# USB.net
KiCad netlist of a schematic drawn in Altium Designer
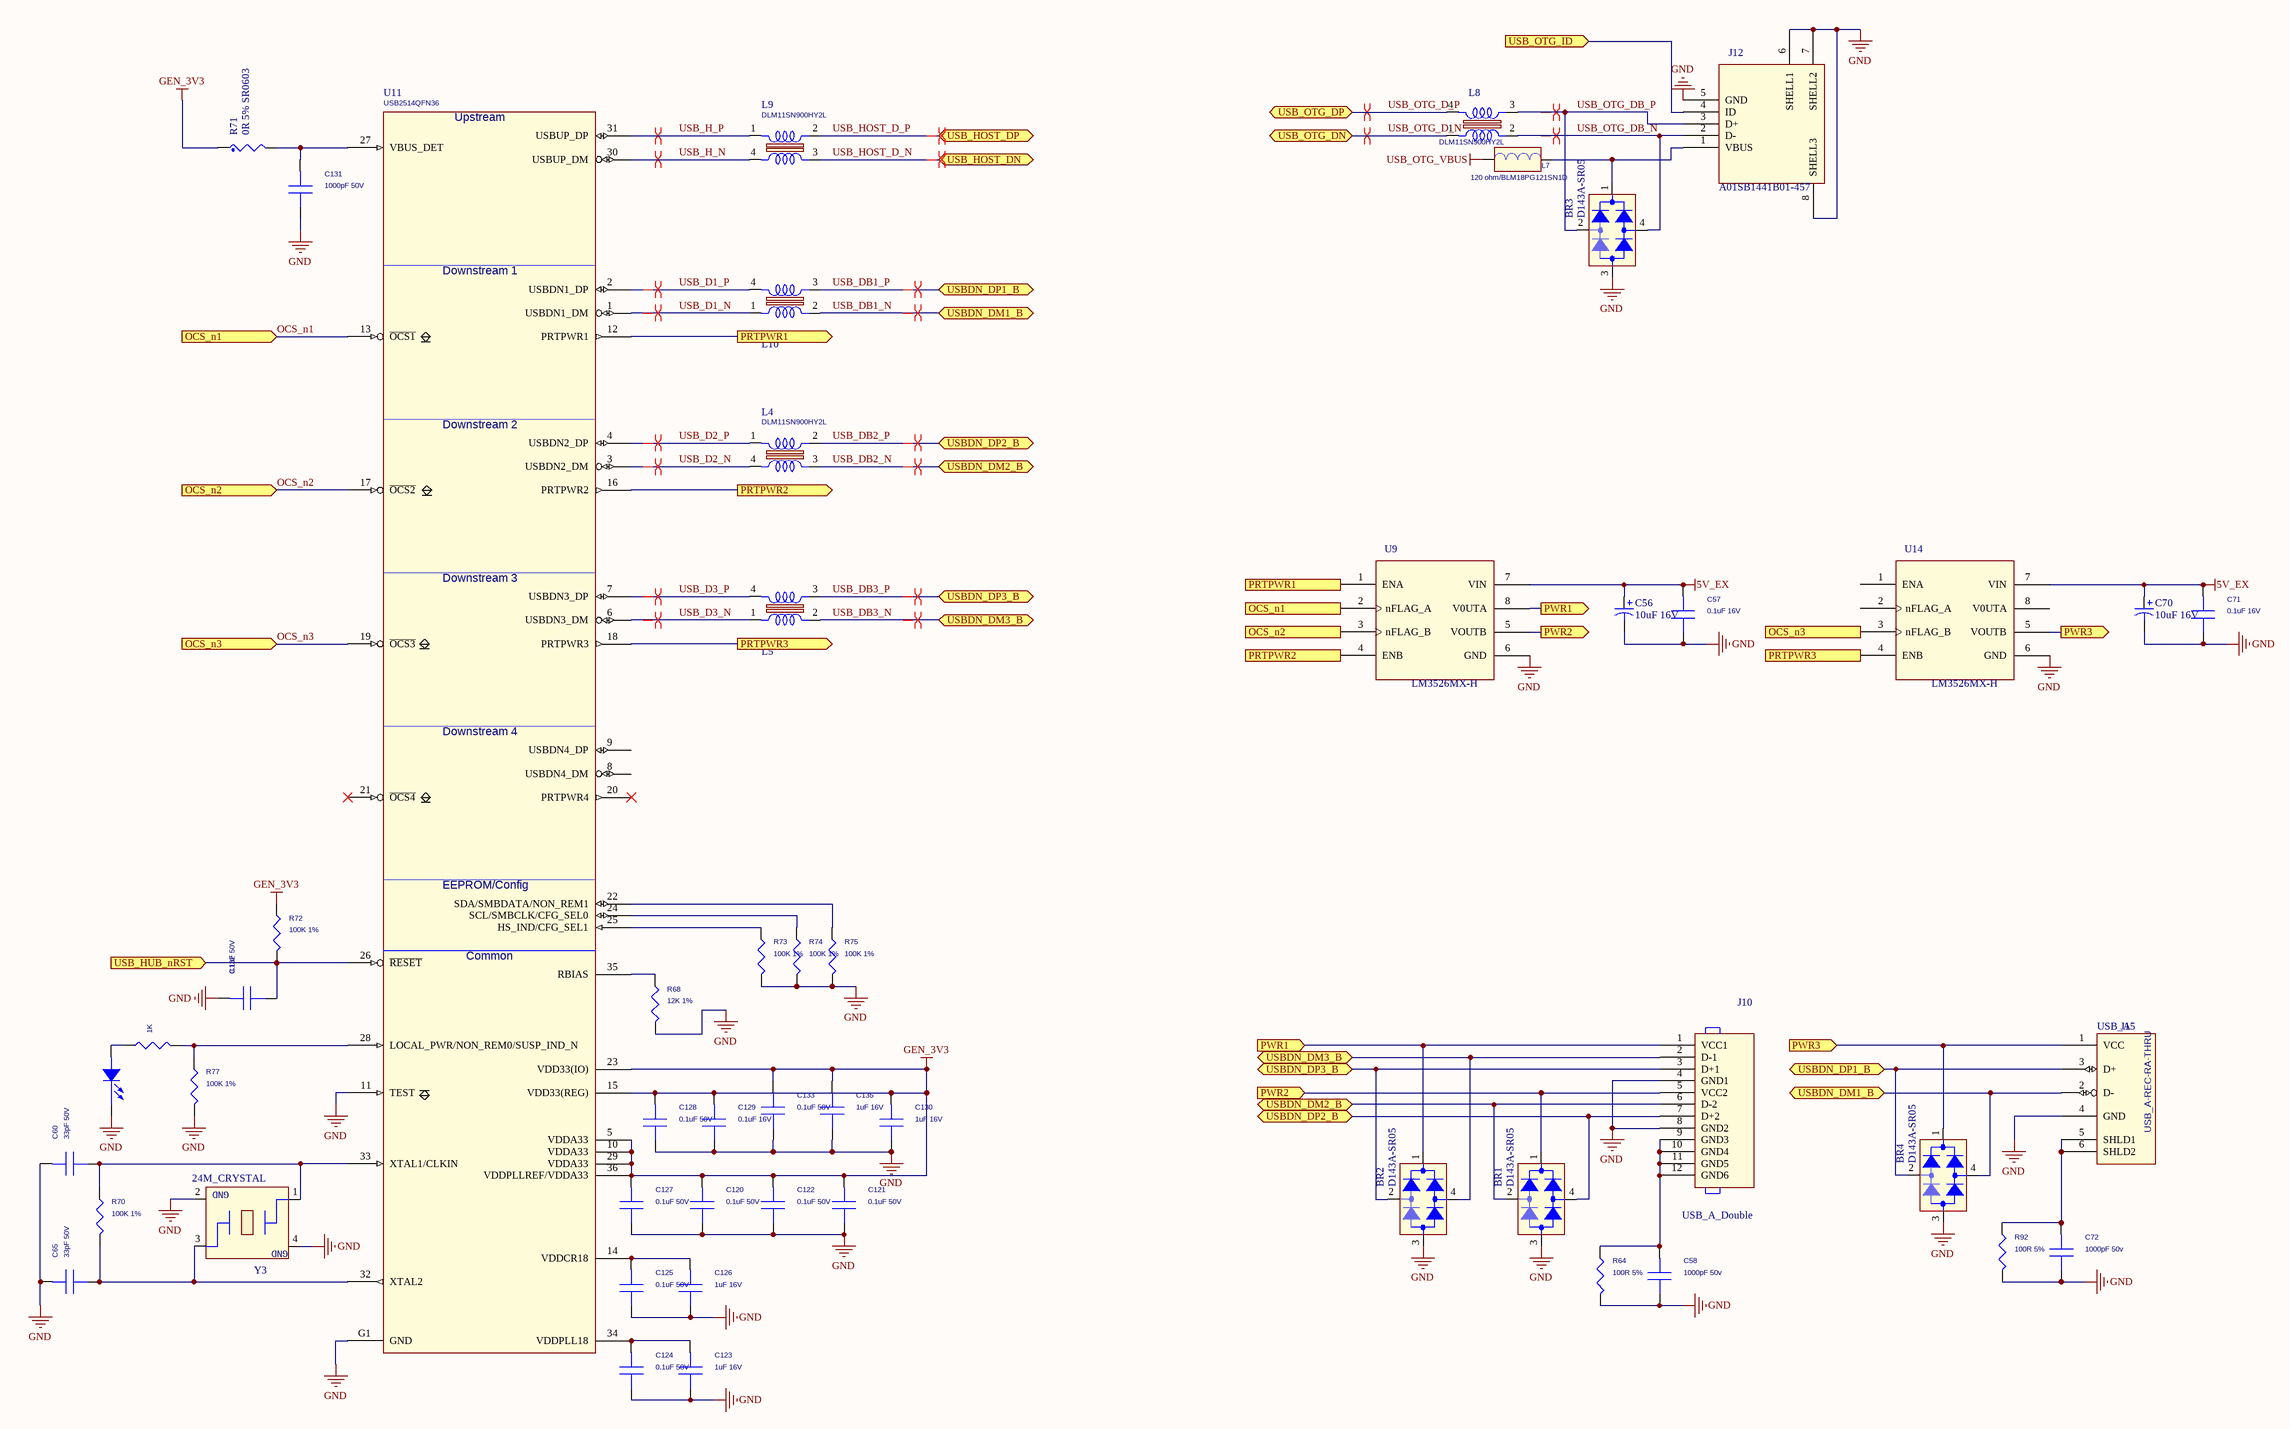
[diagram p0: USB.SchDoc]

(export (version "E")
  (design (tool "Eeschema 10.0.6"))
  (components
    (comp (ref "BR1")
      (value "D143A-SR05")
      (footprint "SOT143")
      (description "SOT143")
      (libsource (lib "MY-I.MX6-SCH_Library") (part "DIO_BRIDGE_BGX50A_KCAC_SOT143"))
    )
    (comp (ref "BR2")
      (value "D143A-SR05")
      (footprint "SOT143")
      (description "SOT143")
      (libsource (lib "MY-I.MX6-SCH_Library") (part "DIO_BRIDGE_BGX50A_KCAC_SOT143"))
    )
    (comp (ref "BR3")
      (value "D143A-SR05")
      (footprint "SOT143")
      (description "SOT143")
      (libsource (lib "MY-I.MX6-SCH_Library") (part "DIO_BRIDGE_BGX50A_KCAC_SOT143"))
    )
    (comp (ref "BR4")
      (value "D143A-SR05")
      (footprint "SOT143")
      (description "SOT143")
      (libsource (lib "MY-I.MX6-SCH_Library") (part "DIO_BRIDGE_BGX50A_KCAC_SOT143"))
    )
    (comp (ref "C56")
      (value "10uF 16V")
      (footprint "SC0805")
      (description "Polarized Capacitor (Radial)")
      (fields (field (name "PUBLISHER") "Altium Limited"))
      (libsource (lib "Miscellaneous Devices") (part "Cap Pol1"))
    )
    (comp (ref "C57")
      (value "0.1uF 16V")
      (footprint "SC0603")
      (description "Capacitor, 0.1uF, 50V, 10%, X5R, 0603")
      (fields (field (name "VOLTAGE") "6.3V") (field (name "TOLERANCE") "10%"))
      (libsource (lib "MY-I.MX6-SCH_Library") (part "0.1uF-6.3V-10%-X5R-0402"))
    )
    (comp (ref "C58")
      (value "1000pF 50v")
      (footprint "SC0603")
      (description "Capacitor, 0.1uF, 50V, 10%, X5R, 0603")
      (fields (field (name "VOLTAGE") "6.3V") (field (name "TOLERANCE") "10%"))
      (libsource (lib "MY-I.MX6-SCH_Library") (part "0.1uF-6.3V-10%-X5R-0402"))
    )
    (comp (ref "C60")
      (value "33pF 50V")
      (footprint "SC0603")
      (description "Capacitor, 0.1uF, 50V, 10%, X5R, 0603")
      (fields (field (name "VOLTAGE") "6.3V") (field (name "TOLERANCE") "10%"))
      (libsource (lib "MY-I.MX6-SCH_Library") (part "0.1uF-6.3V-10%-X5R-0402"))
    )
    (comp (ref "C65")
      (value "33pF 50V")
      (footprint "SC0603")
      (description "Capacitor, 0.1uF, 50V, 10%, X5R, 0603")
      (fields (field (name "VOLTAGE") "6.3V") (field (name "TOLERANCE") "10%"))
      (libsource (lib "MY-I.MX6-SCH_Library") (part "0.1uF-6.3V-10%-X5R-0402"))
    )
    (comp (ref "C70")
      (value "10uF 16V")
      (footprint "SC0805")
      (description "Polarized Capacitor (Radial)")
      (fields (field (name "PUBLISHER") "Altium Limited"))
      (libsource (lib "Miscellaneous Devices") (part "Cap Pol1"))
    )
    (comp (ref "C71")
      (value "0.1uF 16V")
      (footprint "SC0603")
      (description "Capacitor, 0.1uF, 50V, 10%, X5R, 0603")
      (fields (field (name "VOLTAGE") "6.3V") (field (name "TOLERANCE") "10%"))
      (libsource (lib "MY-I.MX6-SCH_Library") (part "0.1uF-6.3V-10%-X5R-0402"))
    )
    (comp (ref "C72")
      (value "1000pF 50v")
      (footprint "SC0603")
      (description "Capacitor, 0.1uF, 50V, 10%, X5R, 0603")
      (fields (field (name "VOLTAGE") "6.3V") (field (name "TOLERANCE") "10%"))
      (libsource (lib "MY-I.MX6-SCH_Library") (part "0.1uF-6.3V-10%-X5R-0402"))
    )
    (comp (ref "C120")
      (value "0.1uF 50V")
      (footprint "SC0603")
      (description "Capacitor, 0.1uF, 50V, 10%, X5R, 0603")
      (fields (field (name "VOLTAGE") "6.3V") (field (name "TOLERANCE") "10%"))
      (libsource (lib "MY-I.MX6-SCH_Library") (part "0.1uF-6.3V-10%-X5R-0402"))
    )
    (comp (ref "C121")
      (value "0.1uF 50V")
      (footprint "SC0603")
      (description "Capacitor, 0.1uF, 50V, 10%, X5R, 0603")
      (fields (field (name "VOLTAGE") "6.3V") (field (name "TOLERANCE") "10%"))
      (libsource (lib "MY-I.MX6-SCH_Library") (part "0.1uF-6.3V-10%-X5R-0402"))
    )
    (comp (ref "C122")
      (value "0.1uF 50V")
      (footprint "SC0603")
      (description "Capacitor, 0.1uF, 50V, 10%, X5R, 0603")
      (fields (field (name "VOLTAGE") "6.3V") (field (name "TOLERANCE") "10%"))
      (libsource (lib "MY-I.MX6-SCH_Library") (part "0.1uF-6.3V-10%-X5R-0402"))
    )
    (comp (ref "C123")
      (value "1uF 16V")
      (footprint "SC0603")
      (description "Capacitor, 1uF, 16V, 10%, X5R, 0603")
      (fields (field (name "VOLTAGE") "6.3V") (field (name "TOLERANCE") "10%"))
      (libsource (lib "MY-I.MX6-SCH_Library") (part "0.1uF-6.3V-10%-X5R-0402"))
    )
    (comp (ref "C124")
      (value "0.1uF 50V")
      (footprint "SC0603")
      (description "Capacitor, 0.1uF, 50V, 10%, X5R, 0603")
      (fields (field (name "VOLTAGE") "6.3V") (field (name "TOLERANCE") "10%"))
      (libsource (lib "MY-I.MX6-SCH_Library") (part "0.1uF-6.3V-10%-X5R-0402"))
    )
    (comp (ref "C125")
      (value "0.1uF 50V")
      (footprint "SC0603")
      (description "Capacitor, 0.1uF, 50V, 10%, X5R, 0603")
      (fields (field (name "VOLTAGE") "6.3V") (field (name "TOLERANCE") "10%"))
      (libsource (lib "MY-I.MX6-SCH_Library") (part "0.1uF-6.3V-10%-X5R-0402"))
    )
    (comp (ref "C126")
      (value "1uF 16V")
      (footprint "SC0603")
      (description "Capacitor, 1uF, 16V, 10%, X5R, 0603")
      (fields (field (name "VOLTAGE") "6.3V") (field (name "TOLERANCE") "10%"))
      (libsource (lib "MY-I.MX6-SCH_Library") (part "0.1uF-6.3V-10%-X5R-0402"))
    )
    (comp (ref "C127")
      (value "0.1uF 50V")
      (footprint "SC0603")
      (description "Capacitor, 0.1uF, 50V, 10%, X5R, 0603")
      (fields (field (name "VOLTAGE") "6.3V") (field (name "TOLERANCE") "10%"))
      (libsource (lib "MY-I.MX6-SCH_Library") (part "0.1uF-6.3V-10%-X5R-0402"))
    )
    (comp (ref "C128")
      (value "0.1uF 50V")
      (footprint "SC0603")
      (description "Capacitor, 0.1uF, 50V, 10%, X5R, 0603")
      (fields (field (name "VOLTAGE") "6.3V") (field (name "TOLERANCE") "10%"))
      (libsource (lib "MY-I.MX6-SCH_Library") (part "0.1uF-6.3V-10%-X5R-0402"))
    )
    (comp (ref "C129")
      (value "0.1uF 16V")
      (footprint "SC0603")
      (description "Capacitor, 0.1uF, 50V, 10%, X5R, 0603")
      (fields (field (name "VOLTAGE") "6.3V") (field (name "TOLERANCE") "10%"))
      (libsource (lib "MY-I.MX6-SCH_Library") (part "0.1uF-6.3V-10%-X5R-0402"))
    )
    (comp (ref "C130")
      (value "1uF 16V")
      (footprint "SC0603")
      (description "Capacitor,1uF, 16V, 10%, X5R, 0603")
      (fields (field (name "VOLTAGE") "6.3V") (field (name "TOLERANCE") "10%"))
      (libsource (lib "MY-I.MX6-SCH_Library") (part "0.1uF-6.3V-10%-X5R-0402"))
    )
    (comp (ref "C131")
      (value "1000pF 50V")
      (footprint "SC0603")
      (description "Capacitor, 0.1uF, 50V, 10%, X5R, 0603")
      (fields (field (name "VOLTAGE") "6.3V") (field (name "TOLERANCE") "10%"))
      (libsource (lib "MY-I.MX6-SCH_Library") (part "0.1uF-6.3V-10%-X5R-0402"))
    )
    (comp (ref "C132")
      (value "0.1uF 50V")
      (footprint "SC0603")
      (description "Capacitor, 0.1uF, 50V, 10%, X5R, 0603")
      (fields (field (name "VOLTAGE") "6.3V") (field (name "TOLERANCE") "10%"))
      (libsource (lib "MY-I.MX6-SCH_Library") (part "0.1uF-6.3V-10%-X5R-0402"))
    )
    (comp (ref "C133")
      (value "0.1uF 50V")
      (footprint "SC0603")
      (description "Capacitor, 0.1uF, 50V, 10%, X5R, 0603")
      (fields (field (name "VOLTAGE") "6.3V") (field (name "TOLERANCE") "10%"))
      (libsource (lib "MY-I.MX6-SCH_Library") (part "0.1uF-6.3V-10%-X5R-0402"))
    )
    (comp (ref "C135")
      (value "1uF 16V")
      (footprint "SC0603")
      (description "Capacitor, 1uF, 50V, 10%, X5R, 0603")
      (fields (field (name "VOLTAGE") "6.3V") (field (name "TOLERANCE") "10%"))
      (libsource (lib "MY-I.MX6-SCH_Library") (part "0.1uF-6.3V-10%-X5R-0402"))
    )
    (comp (ref "D15")
      (value "LED_RED")
      (footprint "SD0603")
      (libsource (lib "MY-I.MX6-SCH_Library") (part "LED"))
    )
    (comp (ref "J10")
      (value "USB_A_Double")
      (footprint "DUSB-TYPEA-LIANSHENG")
      (description "DUSB-TypeA-LianSheng")
      (libsource (lib "MY-I.MX6-SCH_Library") (part "12 HEADER_0"))
    )
    (comp (ref "J12")
      (value "A01SB1441B01-457")
      (footprint "USB-MICRO-B-LIANSHENG-C")
      (description "USB-Micro-B-LianSheng-C")
      (libsource (lib "MY-I.MX6-SCH_Library") (part "MICRO_USB_CONN_0"))
    )
    (comp (ref "J15")
      (value "USB_A")
      (footprint "USB-TYPBEA-ZXHS-V")
      (description "USB-TypbeA-ZXHS-V")
      (libsource (lib "MY-I.MX6-SCH_Library") (part "SKT_USB-A_THRU_RA_0"))
    )
    (comp (ref "L4")
      (value "DLM11SN900HY2L")
      (footprint "SPM2P1X1P3")
      (description "Inductor, Common Mode Choke, DLP11SN900SL2, 0504")
      (libsource (lib "MY-I.MX6-SCH_Library") (part "CHOKE_C-MODE_0"))
    )
    (comp (ref "L5")
      (value "DLM11SN900HY2L")
      (footprint "SPM2P1X1P3")
      (description "Inductor, Common Mode Choke, DLP11SN900SL2, 0504")
      (libsource (lib "") (part "CHOKE_C-MODE_0_1"))
    )
    (comp (ref "L7")
      (value "120 ohm/BLM18PG121SN1D")
      (footprint "SFB0603")
      (description "SFB0603")
      (libsource (lib "MY-I.MX6-SCH_Library") (part "BEAD"))
    )
    (comp (ref "L8")
      (value "DLM11SN900HY2L")
      (footprint "SPM2P1X1P3")
      (description "SPM2p1x1p3")
      (libsource (lib "") (part "CHOKE_C-MODE_0_1"))
    )
    (comp (ref "L9")
      (value "DLM11SN900HY2L")
      (footprint "SPM2P1X1P3")
      (description "Inductor, Common Mode Choke, DLP11SN900SL2, 0504")
      (libsource (lib "MY-I.MX6-SCH_Library") (part "CHOKE_C-MODE_0"))
    )
    (comp (ref "L10")
      (value "DLM11SN900HY2L")
      (footprint "SPM2P1X1P3")
      (description "Inductor, Common Mode Choke, DLP11SN900SL2, 0504")
      (libsource (lib "") (part "CHOKE_C-MODE_0_1"))
    )
    (comp (ref "R64")
      (value "100R 5%")
      (footprint "SR0603")
      (description "Resistor, 100K, 1%, 0603")
      (fields (field (name "TOLERANCE") "5%"))
      (libsource (lib "MY-I.MX6-SCH_Library") (part "100K-1/16W-5%-0603"))
    )
    (comp (ref "R68")
      (value "12K 1%")
      (footprint "SR0603")
      (description "Resistor, 100K, 1%, 0603")
      (fields (field (name "TOLERANCE") "5%"))
      (libsource (lib "MY-I.MX6-SCH_Library") (part "100K-1/16W-5%-0603"))
    )
    (comp (ref "R70")
      (value "100K 1%")
      (footprint "SR0603")
      (description "Resistor, 100K, 1%, 0603")
      (fields (field (name "TOLERANCE") "5%"))
      (libsource (lib "MY-I.MX6-SCH_Library") (part "100K-1/16W-5%-0603"))
    )
    (comp (ref "R71")
      (value "0R 5% SR0603")
      (footprint "SR0603")
      (libsource (lib "MY-I.MX6-SCH_Library") (part "RES"))
    )
    (comp (ref "R72")
      (value "100K 1%")
      (footprint "SR0603")
      (description "Resistor, 100K, 1%, 0603")
      (fields (field (name "TOLERANCE") "5%"))
      (libsource (lib "MY-I.MX6-SCH_Library") (part "100K-1/16W-5%-0603"))
    )
    (comp (ref "R73")
      (value "100K 1%")
      (footprint "SR0603")
      (description "Resistor, 100K, 1%, 0603")
      (fields (field (name "TOLERANCE") "5%"))
      (libsource (lib "MY-I.MX6-SCH_Library") (part "100K-1/16W-5%-0603"))
    )
    (comp (ref "R74")
      (value "100K 1%")
      (footprint "SR0603")
      (description "Resistor, 100K, 1%, 0603")
      (fields (field (name "TOLERANCE") "5%"))
      (libsource (lib "MY-I.MX6-SCH_Library") (part "100K-1/16W-5%-0603"))
    )
    (comp (ref "R75")
      (value "100K 1%")
      (footprint "SR0603")
      (description "Resistor, 100K, 1%, 0603")
      (fields (field (name "TOLERANCE") "5%"))
      (libsource (lib "MY-I.MX6-SCH_Library") (part "100K-1/16W-5%-0603"))
    )
    (comp (ref "R76")
      (value "1K")
      (footprint "SR0603")
      (description "Resistor, 1K, 5%, 1/16W, 0603")
      (fields (field (name "TOLERANCE") "5%"))
      (libsource (lib "MY-I.MX6-SCH_Library") (part "1.0K-1/16W-5%-0603"))
    )
    (comp (ref "R77")
      (value "100K 1%")
      (footprint "SR0603")
      (description "Resistor, 100K, 1%, 0603")
      (fields (field (name "TOLERANCE") "5%"))
      (libsource (lib "MY-I.MX6-SCH_Library") (part "100K-1/16W-5%-0603"))
    )
    (comp (ref "R92")
      (value "100R 5%")
      (footprint "SR0603")
      (description "Resistor, 100K, 1%, 0603")
      (fields (field (name "TOLERANCE") "5%"))
      (libsource (lib "MY-I.MX6-SCH_Library") (part "100K-1/16W-5%-0603"))
    )
    (comp (ref "U9")
      (value "LM3526MX-H")
      (footprint "SOP8-1p27-5x4")
      (description "SOP8-1p27-5x4")
      (libsource (lib "MY-I.MX6-SCH_Library") (part "LM3526-L"))
    )
    (comp (ref "U11")
      (value "USB2514_QFN36_0")
      (footprint "QFP36-0P5-6X6")
      (description "IC, USB2514, 4 Port USB 2.0 Hub, QFN36")
      (fields (field (name "DEVICE") "USB2514QFN36"))
      (libsource (lib "MY-I.MX6-SCH_Library") (part "USB2514_QFN36_0"))
    )
    (comp (ref "U14")
      (value "LM3526MX-H")
      (footprint "SOP8-1p27-5x4")
      (description "SOP8-1p27-5x4")
      (libsource (lib "MY-I.MX6-SCH_Library") (part "LM3526-L"))
    )
    (comp (ref "Y3")
      (value "24M_CRYSTAL")
      (footprint "SCRY4-3P2X2P5")
      (description "SCRY4-3p2x2p5")
      (libsource (lib "MY-I.MX6-SCH_Library") (part "24M_CRYSTAL"))
    )
  )
  (nets
    (net (code "1") (name "/OCS_n1") (class "Default")
      (node (ref "U11") (pin "13") (pinfunction "~{OCS1}_13") (pintype "input"))
      (node (ref "U9") (pin "2") (pinfunction "nFLAG_A_2") (pintype "passive"))
    )
    (net (code "2") (name "/OCS_n2") (class "Default")
      (node (ref "U11") (pin "17") (pinfunction "~{OCS2}_17") (pintype "input"))
      (node (ref "U9") (pin "3") (pinfunction "nFLAG_B_3") (pintype "passive"))
    )
    (net (code "3") (name "/OCS_n3") (class "Default")
      (node (ref "U11") (pin "19") (pinfunction "~{OCS3}_19") (pintype "input"))
      (node (ref "U14") (pin "3") (pinfunction "nFLAG_B_3") (pintype "passive"))
    )
    (net (code "4") (name "/PRTPWR1") (class "Default")
      (node (ref "U11") (pin "12") (pinfunction "PRTPWR1_12") (pintype "output"))
      (node (ref "U9") (pin "1") (pinfunction "ENA_1") (pintype "passive"))
    )
    (net (code "5") (name "/PRTPWR2") (class "Default")
      (node (ref "U11") (pin "16") (pinfunction "PRTPWR2_16") (pintype "output"))
      (node (ref "U9") (pin "4") (pinfunction "ENB_4") (pintype "passive"))
    )
    (net (code "6") (name "/PRTPWR3") (class "Default")
      (node (ref "U11") (pin "18") (pinfunction "PRTPWR3_18") (pintype "output"))
      (node (ref "U14") (pin "4") (pinfunction "ENB_4") (pintype "passive"))
    )
    (net (code "7") (name "/PWR1") (class "Default")
      (node (ref "BR2") (pin "1") (pinfunction "1_1") (pintype "passive"))
      (node (ref "J10") (pin "1") (pinfunction "VCC1_1") (pintype "passive"))
      (node (ref "U9") (pin "8") (pinfunction "V0UTA_8") (pintype "passive"))
    )
    (net (code "8") (name "/PWR2") (class "Default")
      (node (ref "BR1") (pin "1") (pinfunction "1_1") (pintype "passive"))
      (node (ref "J10") (pin "5") (pinfunction "VCC2_5") (pintype "passive"))
      (node (ref "U9") (pin "5") (pinfunction "VOUTB_5") (pintype "passive"))
    )
    (net (code "9") (name "/PWR3") (class "Default")
      (node (ref "BR4") (pin "1") (pinfunction "1_1") (pintype "passive"))
      (node (ref "J15") (pin "1") (pinfunction "VCC_1") (pintype "passive"))
      (node (ref "U14") (pin "5") (pinfunction "VOUTB_5") (pintype "passive"))
    )
    (net (code "10") (name "/USB_D1_N") (class "Default")
      (node (ref "L10") (pin "1") (pinfunction "1_1") (pintype "passive"))
      (node (ref "U11") (pin "1") (pinfunction "USBDN1_DM_1") (pintype "bidirectional"))
    )
    (net (code "11") (name "/USB_D1_P") (class "Default")
      (node (ref "L10") (pin "4") (pinfunction "4_4") (pintype "passive"))
      (node (ref "U11") (pin "2") (pinfunction "USBDN1_DP_2") (pintype "bidirectional"))
    )
    (net (code "12") (name "/USB_D2_N") (class "Default")
      (node (ref "L4") (pin "4") (pinfunction "4_4") (pintype "passive"))
      (node (ref "U11") (pin "3") (pinfunction "USBDN2_DM_3") (pintype "bidirectional"))
    )
    (net (code "13") (name "/USB_D2_P") (class "Default")
      (node (ref "L4") (pin "1") (pinfunction "1_1") (pintype "passive"))
      (node (ref "U11") (pin "4") (pinfunction "USBDN2_DP_4") (pintype "bidirectional"))
    )
    (net (code "14") (name "/USB_D3_N") (class "Default")
      (node (ref "L5") (pin "1") (pinfunction "1_1") (pintype "passive"))
      (node (ref "U11") (pin "6") (pinfunction "USBDN3_DM_6") (pintype "bidirectional"))
    )
    (net (code "15") (name "/USB_D3_P") (class "Default")
      (node (ref "L5") (pin "4") (pinfunction "4_4") (pintype "passive"))
      (node (ref "U11") (pin "7") (pinfunction "USBDN3_DP_7") (pintype "bidirectional"))
    )
    (net (code "16") (name "/USB_DB1_N") (class "Default")
      (node (ref "BR4") (pin "4") (pinfunction "4_4") (pintype "passive"))
      (node (ref "J15") (pin "2") (pinfunction "D-_2") (pintype "bidirectional"))
      (node (ref "L10") (pin "2") (pinfunction "2_2") (pintype "passive"))
    )
    (net (code "17") (name "/USB_DB1_P") (class "Default")
      (node (ref "BR4") (pin "2") (pinfunction "2_2") (pintype "passive"))
      (node (ref "J15") (pin "3") (pinfunction "D+_3") (pintype "bidirectional"))
      (node (ref "L10") (pin "3") (pinfunction "3_3") (pintype "passive"))
    )
    (net (code "18") (name "/USB_DB2_N") (class "Default")
      (node (ref "BR1") (pin "2") (pinfunction "2_2") (pintype "passive"))
      (node (ref "J10") (pin "6") (pinfunction "D-2_6") (pintype "passive"))
      (node (ref "L4") (pin "3") (pinfunction "3_3") (pintype "passive"))
    )
    (net (code "19") (name "/USB_DB2_P") (class "Default")
      (node (ref "BR1") (pin "4") (pinfunction "4_4") (pintype "passive"))
      (node (ref "J10") (pin "7") (pinfunction "D+2_7") (pintype "passive"))
      (node (ref "L4") (pin "2") (pinfunction "2_2") (pintype "passive"))
    )
    (net (code "20") (name "/USB_DB3_N") (class "Default")
      (node (ref "BR2") (pin "4") (pinfunction "4_4") (pintype "passive"))
      (node (ref "J10") (pin "2") (pinfunction "D-1_2") (pintype "passive"))
      (node (ref "L5") (pin "2") (pinfunction "2_2") (pintype "passive"))
    )
    (net (code "21") (name "/USB_DB3_P") (class "Default")
      (node (ref "BR2") (pin "2") (pinfunction "2_2") (pintype "passive"))
      (node (ref "J10") (pin "3") (pinfunction "D+1_3") (pintype "passive"))
      (node (ref "L5") (pin "3") (pinfunction "3_3") (pintype "passive"))
    )
    (net (code "22") (name "/USB_HOST_D_N") (class "Default")
      (node (ref "L9") (pin "3") (pinfunction "3_3") (pintype "passive"))
    )
    (net (code "23") (name "/USB_HOST_D_P") (class "Default")
      (node (ref "L9") (pin "2") (pinfunction "2_2") (pintype "passive"))
    )
    (net (code "24") (name "/USB_HUB_nRST") (class "Default")
      (node (ref "C132") (pin "2") (pinfunction "2_2") (pintype "passive"))
      (node (ref "R72") (pin "2") (pinfunction "2_2") (pintype "passive"))
      (node (ref "U11") (pin "26") (pinfunction "~{RESET}_26") (pintype "input"))
    )
    (net (code "25") (name "/USB_H_N") (class "Default")
      (node (ref "L9") (pin "4") (pinfunction "4_4") (pintype "passive"))
      (node (ref "U11") (pin "30") (pinfunction "USBUP_DM_30") (pintype "bidirectional"))
    )
    (net (code "26") (name "/USB_H_P") (class "Default")
      (node (ref "L9") (pin "1") (pinfunction "1_1") (pintype "passive"))
      (node (ref "U11") (pin "31") (pinfunction "USBUP_DP_31") (pintype "bidirectional"))
    )
    (net (code "27") (name "/USB_OTG_DB_N") (class "Default")
      (node (ref "BR3") (pin "4") (pinfunction "4_4") (pintype "passive"))
      (node (ref "J12") (pin "2") (pinfunction "D-_2") (pintype "passive"))
      (node (ref "L8") (pin "2") (pinfunction "2_2") (pintype "passive"))
    )
    (net (code "28") (name "/USB_OTG_DB_P") (class "Default")
      (node (ref "BR3") (pin "2") (pinfunction "2_2") (pintype "passive"))
      (node (ref "J12") (pin "3") (pinfunction "D+_3") (pintype "passive"))
      (node (ref "L8") (pin "3") (pinfunction "3_3") (pintype "passive"))
    )
    (net (code "29") (name "/USB_OTG_D_N") (class "Default")
      (node (ref "L8") (pin "1") (pinfunction "1_1") (pintype "passive"))
    )
    (net (code "30") (name "/USB_OTG_D_P") (class "Default")
      (node (ref "L8") (pin "4") (pinfunction "4_4") (pintype "passive"))
    )
    (net (code "31") (name "/USB_OTG_ID") (class "Default")
      (node (ref "J12") (pin "4") (pinfunction "ID_4") (pintype "passive"))
    )
    (net (code "32") (name "5V_EX") (class "Default")
      (node (ref "C56") (pin "1") (pinfunction "1_1") (pintype "passive"))
      (node (ref "C57") (pin "1") (pinfunction "1_1") (pintype "passive"))
      (node (ref "C70") (pin "1") (pinfunction "1_1") (pintype "passive"))
      (node (ref "C71") (pin "1") (pinfunction "1_1") (pintype "passive"))
      (node (ref "U14") (pin "7") (pinfunction "VIN_7") (pintype "passive"))
      (node (ref "U9") (pin "7") (pinfunction "VIN_7") (pintype "passive"))
    )
    (net (code "33") (name "GEN_3V3") (class "Default")
      (node (ref "C120") (pin "1") (pinfunction "1_1") (pintype "passive"))
      (node (ref "C121") (pin "1") (pinfunction "1_1") (pintype "passive"))
      (node (ref "C122") (pin "1") (pinfunction "1_1") (pintype "passive"))
      (node (ref "C127") (pin "1") (pinfunction "1_1") (pintype "passive"))
      (node (ref "C128") (pin "1") (pinfunction "1_1") (pintype "passive"))
      (node (ref "C129") (pin "1") (pinfunction "1_1") (pintype "passive"))
      (node (ref "C130") (pin "1") (pinfunction "1_1") (pintype "passive"))
      (node (ref "C133") (pin "1") (pinfunction "1_1") (pintype "passive"))
      (node (ref "C135") (pin "1") (pinfunction "1_1") (pintype "passive"))
      (node (ref "R71") (pin "1") (pinfunction "1_1") (pintype "passive"))
      (node (ref "R72") (pin "1") (pinfunction "1_1") (pintype "passive"))
      (node (ref "U11") (pin "10") (pinfunction "VDDA33_10") (pintype "power_in"))
      (node (ref "U11") (pin "15") (pinfunction "VDD33(REG)_15") (pintype "power_in"))
      (node (ref "U11") (pin "23") (pinfunction "VDD33(IO)_23") (pintype "power_in"))
      (node (ref "U11") (pin "29") (pinfunction "VDDA33_29") (pintype "power_in"))
      (node (ref "U11") (pin "36") (pinfunction "VDDPLLREF/VDDA33_36") (pintype "power_in"))
      (node (ref "U11") (pin "5") (pinfunction "VDDA33_5") (pintype "power_in"))
    )
    (net (code "34") (name "GND") (class "Default")
      (node (ref "BR1") (pin "3") (pinfunction "3_3") (pintype "passive"))
      (node (ref "BR2") (pin "3") (pinfunction "3_3") (pintype "passive"))
      (node (ref "BR3") (pin "3") (pinfunction "3_3") (pintype "passive"))
      (node (ref "BR4") (pin "3") (pinfunction "3_3") (pintype "passive"))
      (node (ref "C120") (pin "2") (pinfunction "2_2") (pintype "passive"))
      (node (ref "C121") (pin "2") (pinfunction "2_2") (pintype "passive"))
      (node (ref "C122") (pin "2") (pinfunction "2_2") (pintype "passive"))
      (node (ref "C123") (pin "2") (pinfunction "2_2") (pintype "passive"))
      (node (ref "C124") (pin "2") (pinfunction "2_2") (pintype "passive"))
      (node (ref "C125") (pin "2") (pinfunction "2_2") (pintype "passive"))
      (node (ref "C126") (pin "2") (pinfunction "2_2") (pintype "passive"))
      (node (ref "C127") (pin "2") (pinfunction "2_2") (pintype "passive"))
      (node (ref "C128") (pin "2") (pinfunction "2_2") (pintype "passive"))
      (node (ref "C129") (pin "2") (pinfunction "2_2") (pintype "passive"))
      (node (ref "C130") (pin "2") (pinfunction "2_2") (pintype "passive"))
      (node (ref "C131") (pin "2") (pinfunction "2_2") (pintype "passive"))
      (node (ref "C132") (pin "1") (pinfunction "1_1") (pintype "passive"))
      (node (ref "C133") (pin "2") (pinfunction "2_2") (pintype "passive"))
      (node (ref "C135") (pin "2") (pinfunction "2_2") (pintype "passive"))
      (node (ref "C56") (pin "2") (pinfunction "2_2") (pintype "passive"))
      (node (ref "C57") (pin "2") (pinfunction "2_2") (pintype "passive"))
      (node (ref "C58") (pin "2") (pinfunction "2_2") (pintype "passive"))
      (node (ref "C60") (pin "1") (pinfunction "1_1") (pintype "passive"))
      (node (ref "C65") (pin "1") (pinfunction "1_1") (pintype "passive"))
      (node (ref "C70") (pin "2") (pinfunction "2_2") (pintype "passive"))
      (node (ref "C71") (pin "2") (pinfunction "2_2") (pintype "passive"))
      (node (ref "C72") (pin "2") (pinfunction "2_2") (pintype "passive"))
      (node (ref "D15") (pin "2") (pinfunction "CATHODE_2") (pintype "passive"))
      (node (ref "J10") (pin "4") (pinfunction "GND1_4") (pintype "passive"))
      (node (ref "J10") (pin "8") (pinfunction "GND2_8") (pintype "passive"))
      (node (ref "J12") (pin "5") (pinfunction "GND_5") (pintype "passive"))
      (node (ref "J12") (pin "6") (pinfunction "SHELL1_6") (pintype "passive"))
      (node (ref "J12") (pin "7") (pinfunction "SHELL2_7") (pintype "passive"))
      (node (ref "J12") (pin "8") (pinfunction "SHELL3_8") (pintype "passive"))
      (node (ref "J15") (pin "4") (pinfunction "GND_4") (pintype "passive"))
      (node (ref "R64") (pin "2") (pinfunction "2_2") (pintype "passive"))
      (node (ref "R68") (pin "2") (pinfunction "2_2") (pintype "passive"))
      (node (ref "R73") (pin "2") (pinfunction "2_2") (pintype "passive"))
      (node (ref "R74") (pin "2") (pinfunction "2_2") (pintype "passive"))
      (node (ref "R75") (pin "2") (pinfunction "2_2") (pintype "passive"))
      (node (ref "R77") (pin "2") (pinfunction "2_2") (pintype "passive"))
      (node (ref "R92") (pin "2") (pinfunction "2_2") (pintype "passive"))
      (node (ref "U11") (pin "11") (pinfunction "TEST_11") (pintype "input"))
      (node (ref "U11") (pin "G1") (pinfunction "GND_G1") (pintype "passive"))
      (node (ref "U14") (pin "6") (pinfunction "GND_6") (pintype "passive"))
      (node (ref "U9") (pin "6") (pinfunction "GND_6") (pintype "passive"))
      (node (ref "Y3") (pin "2") (pinfunction "GND2_2") (pintype "passive"))
      (node (ref "Y3") (pin "4") (pinfunction "GND1_4") (pintype "passive"))
    )
    (net (code "35") (name "Net-(D15-ANODE)") (class "Default")
      (node (ref "D15") (pin "1") (pinfunction "ANODE_1") (pintype "passive"))
      (node (ref "R76") (pin "1") (pinfunction "1_1") (pintype "passive"))
    )
    (net (code "36") (name "Net-(J10-GND3)") (class "Default")
      (node (ref "C58") (pin "1") (pinfunction "1_1") (pintype "passive"))
      (node (ref "J10") (pin "10") (pinfunction "GND4_10") (pintype "passive"))
      (node (ref "J10") (pin "11") (pinfunction "GND5_11") (pintype "passive"))
      (node (ref "J10") (pin "12") (pinfunction "GND6_12") (pintype "passive"))
      (node (ref "J10") (pin "9") (pinfunction "GND3_9") (pintype "passive"))
      (node (ref "R64") (pin "1") (pinfunction "1_1") (pintype "passive"))
    )
    (net (code "37") (name "Net-(J12-VBUS)") (class "Default")
      (node (ref "BR3") (pin "1") (pinfunction "1_1") (pintype "passive"))
      (node (ref "J12") (pin "1") (pinfunction "VBUS_1") (pintype "passive"))
      (node (ref "L7") (pin "2") (pinfunction "2_2") (pintype "passive"))
    )
    (net (code "38") (name "Net-(J15-SHLD1)") (class "Default")
      (node (ref "C72") (pin "1") (pinfunction "1_1") (pintype "passive"))
      (node (ref "J15") (pin "5") (pinfunction "SHLD1_5") (pintype "passive"))
      (node (ref "J15") (pin "6") (pinfunction "SHLD2_6") (pintype "passive"))
      (node (ref "R92") (pin "1") (pinfunction "1_1") (pintype "passive"))
    )
    (net (code "39") (name "Net-(U11-HS_IND{slash}CFG_SEL1)") (class "Default")
      (node (ref "R73") (pin "1") (pinfunction "1_1") (pintype "passive"))
      (node (ref "U11") (pin "25") (pinfunction "HS_IND/CFG_SEL1_25") (pintype "input"))
    )
    (net (code "40") (name "Net-(U11-LOCAL_PWR{slash}NON_REM0{slash}SUSP_IND_N)") (class "Default")
      (node (ref "R76") (pin "2") (pinfunction "2_2") (pintype "passive"))
      (node (ref "R77") (pin "1") (pinfunction "1_1") (pintype "passive"))
      (node (ref "U11") (pin "28") (pinfunction "LOCAL_PWR/NON_REM0/SUSP_IND_N_28") (pintype "input"))
    )
    (net (code "41") (name "Net-(U11-RBIAS)") (class "Default")
      (node (ref "R68") (pin "1") (pinfunction "1_1") (pintype "passive"))
      (node (ref "U11") (pin "35") (pinfunction "RBIAS_35") (pintype "passive"))
    )
    (net (code "42") (name "Net-(U11-SCL{slash}SMBCLK{slash}CFG_SEL0)") (class "Default")
      (node (ref "R74") (pin "1") (pinfunction "1_1") (pintype "passive"))
      (node (ref "U11") (pin "24") (pinfunction "SCL/SMBCLK/CFG_SEL0_24") (pintype "bidirectional"))
    )
    (net (code "43") (name "Net-(U11-SDA{slash}SMBDATA{slash}NON_REM1)") (class "Default")
      (node (ref "R75") (pin "1") (pinfunction "1_1") (pintype "passive"))
      (node (ref "U11") (pin "22") (pinfunction "SDA/SMBDATA/NON_REM1_22") (pintype "bidirectional"))
    )
    (net (code "44") (name "Net-(U11-VBUS_DET)") (class "Default")
      (node (ref "C131") (pin "1") (pinfunction "1_1") (pintype "passive"))
      (node (ref "R71") (pin "2") (pinfunction "2_2") (pintype "passive"))
      (node (ref "U11") (pin "27") (pinfunction "VBUS_DET_27") (pintype "input"))
    )
    (net (code "45") (name "Net-(U11-VDDCR18)") (class "Default")
      (node (ref "C125") (pin "1") (pinfunction "1_1") (pintype "passive"))
      (node (ref "C126") (pin "1") (pinfunction "1_1") (pintype "passive"))
      (node (ref "U11") (pin "14") (pinfunction "VDDCR18_14") (pintype "power_in"))
    )
    (net (code "46") (name "Net-(U11-VDDPLL18)") (class "Default")
      (node (ref "C123") (pin "1") (pinfunction "1_1") (pintype "passive"))
      (node (ref "C124") (pin "1") (pinfunction "1_1") (pintype "passive"))
      (node (ref "U11") (pin "34") (pinfunction "VDDPLL18_34") (pintype "power_in"))
    )
    (net (code "47") (name "Net-(U11-XTAL1{slash}CLKIN)") (class "Default")
      (node (ref "C60") (pin "2") (pinfunction "2_2") (pintype "passive"))
      (node (ref "R70") (pin "1") (pinfunction "1_1") (pintype "passive"))
      (node (ref "U11") (pin "33") (pinfunction "XTAL1/CLKIN_33") (pintype "input"))
      (node (ref "Y3") (pin "1") (pinfunction "1_1") (pintype "passive"))
    )
    (net (code "48") (name "Net-(U11-XTAL2)") (class "Default")
      (node (ref "C65") (pin "2") (pinfunction "2_2") (pintype "passive"))
      (node (ref "R70") (pin "2") (pinfunction "2_2") (pintype "passive"))
      (node (ref "U11") (pin "32") (pinfunction "XTAL2_32") (pintype "output"))
      (node (ref "Y3") (pin "3") (pinfunction "3_3") (pintype "passive"))
    )
    (net (code "49") (name "USB_OTG_VBUS") (class "Default")
      (node (ref "L7") (pin "1") (pinfunction "1_1") (pintype "passive"))
    )
    (net (code "50") (name "unconnected-(U11-PRTPWR4-Pad20)") (class "Default")
      (node (ref "U11") (pin "20") (pinfunction "PRTPWR4_20") (pintype "output+no_connect"))
    )
    (net (code "51") (name "unconnected-(U11-USBDN4_DM-Pad8)") (class "Default")
      (node (ref "U11") (pin "8") (pinfunction "USBDN4_DM_8") (pintype "bidirectional"))
    )
    (net (code "52") (name "unconnected-(U11-USBDN4_DP-Pad9)") (class "Default")
      (node (ref "U11") (pin "9") (pinfunction "USBDN4_DP_9") (pintype "bidirectional"))
    )
    (net (code "53") (name "unconnected-(U11-~{OCS4}-Pad21)") (class "Default")
      (node (ref "U11") (pin "21") (pinfunction "~{OCS4}_21") (pintype "input+no_connect"))
    )
    (net (code "54") (name "unconnected-(U14-ENA-Pad1)") (class "Default")
      (node (ref "U14") (pin "1") (pinfunction "ENA_1") (pintype "passive"))
    )
    (net (code "55") (name "unconnected-(U14-V0UTA-Pad8)") (class "Default")
      (node (ref "U14") (pin "8") (pinfunction "V0UTA_8") (pintype "passive"))
    )
    (net (code "56") (name "unconnected-(U14-nFLAG_A-Pad2)") (class "Default")
      (node (ref "U14") (pin "2") (pinfunction "nFLAG_A_2") (pintype "passive"))
    )
  )
)
